# stm32-d40plus.net
KiCad netlist of a schematic drawn in EAGLE
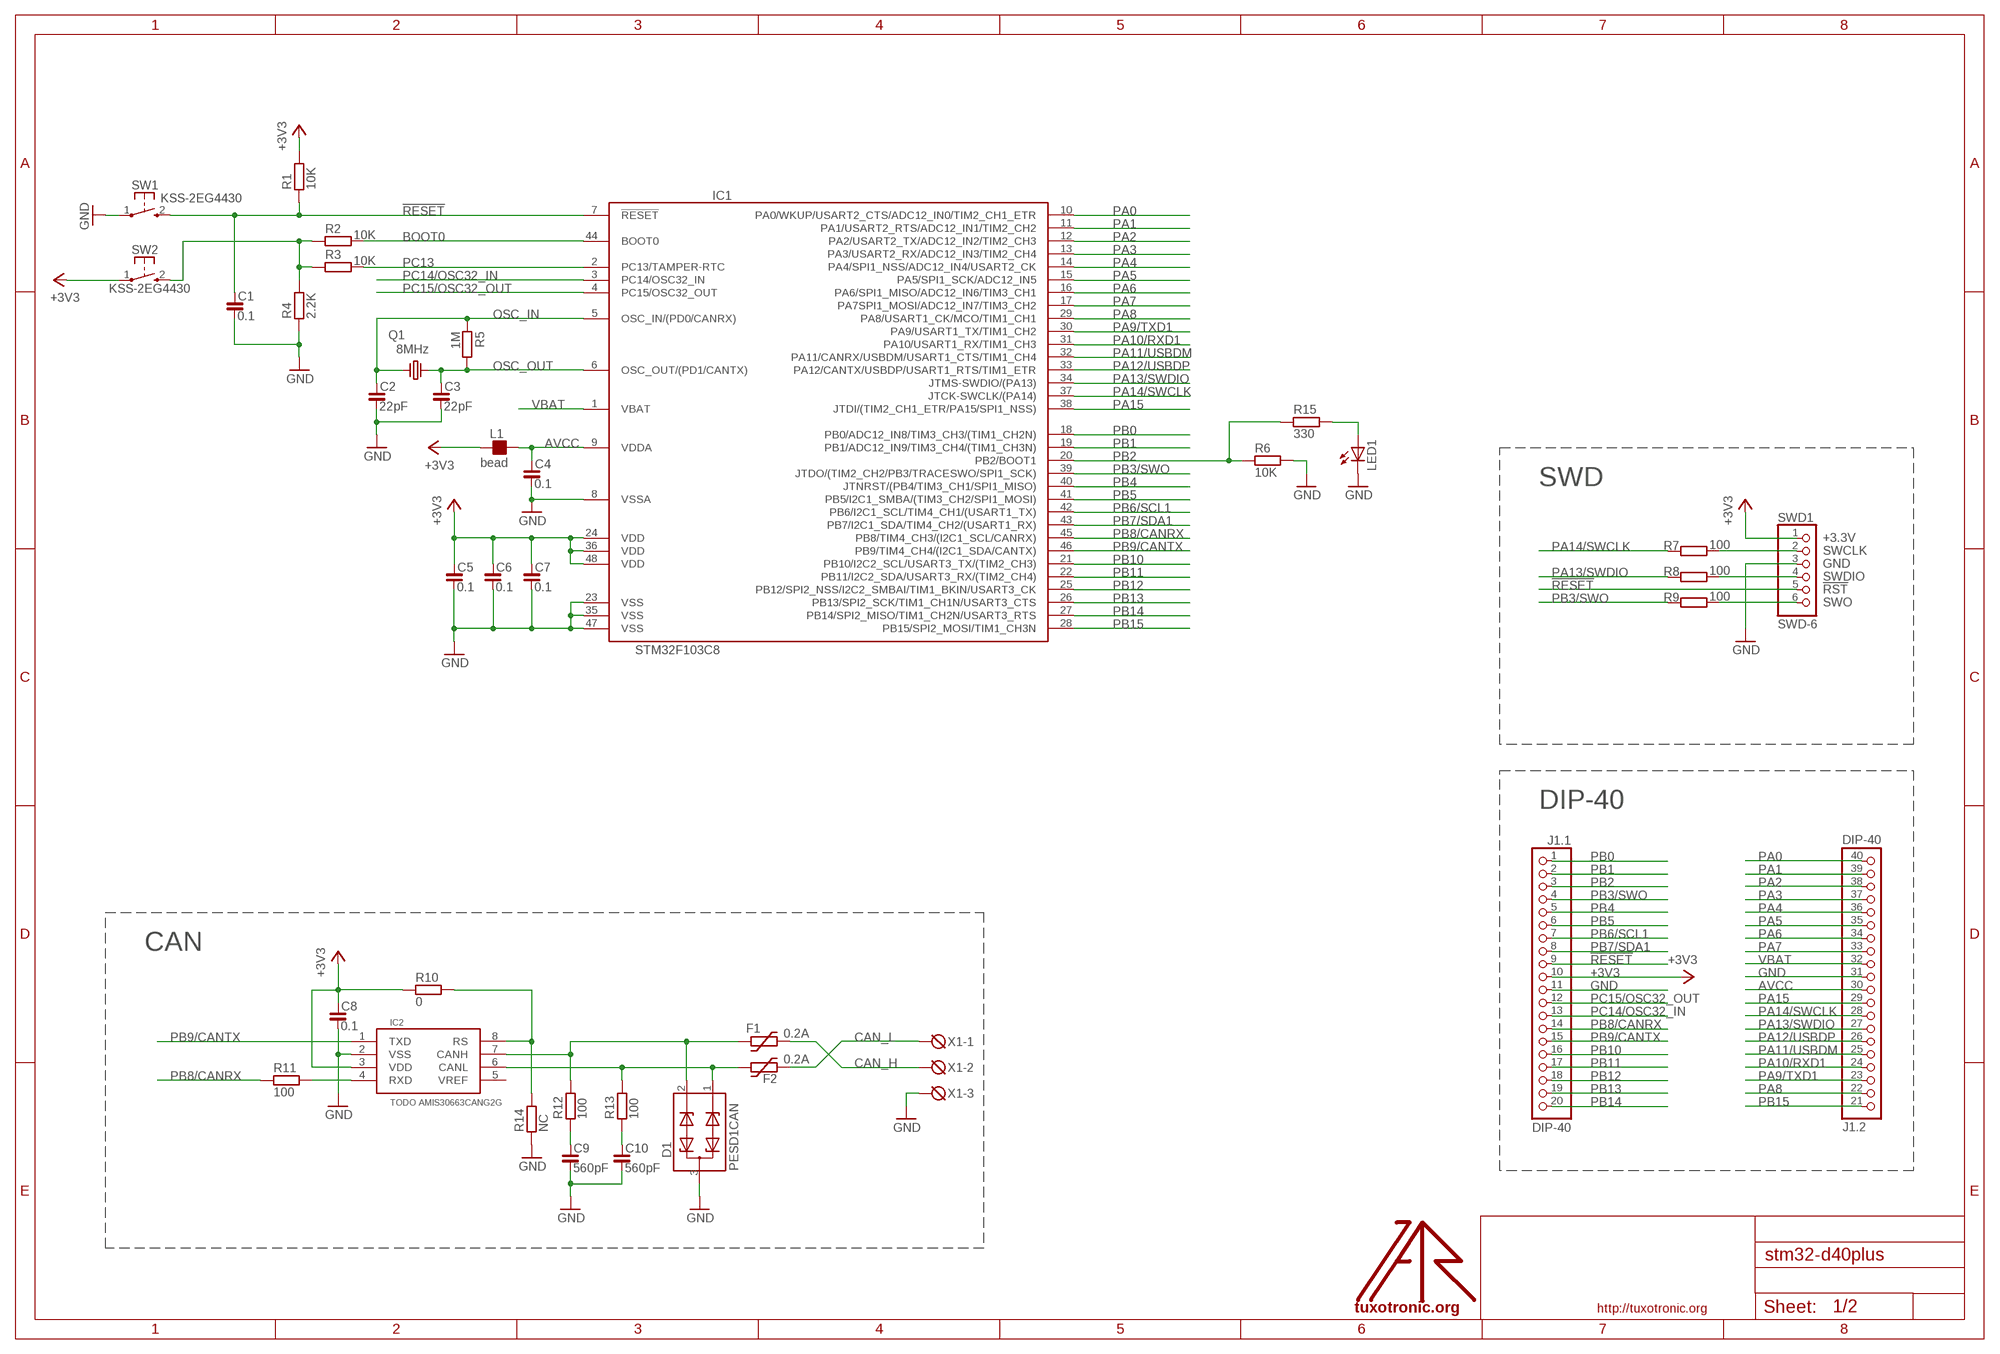
[diagram p0: schematic, sheet 1]
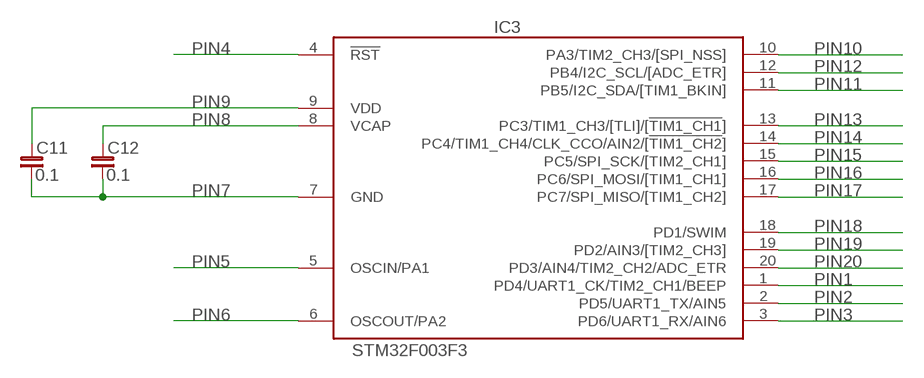
[diagram p1: schematic, sheet 2]

(export (version "E")
  (design (tool "Eeschema 10.0.6"))
  (components
    (comp (ref "C1")
      (value "0.1")
      (footprint "eagle-import:C0603")
      (libsource (lib "eagle-import") (part "C_0603"))
    )
    (comp (ref "C2")
      (value "22pF")
      (footprint "eagle-import:C0603")
      (libsource (lib "eagle-import") (part "C_0603"))
    )
    (comp (ref "C3")
      (value "22pF")
      (footprint "eagle-import:C0603")
      (libsource (lib "eagle-import") (part "C_0603"))
    )
    (comp (ref "C4")
      (value "0.1")
      (footprint "eagle-import:C0603")
      (libsource (lib "eagle-import") (part "C_0603"))
    )
    (comp (ref "C5")
      (value "0.1")
      (footprint "eagle-import:C0603")
      (libsource (lib "eagle-import") (part "C_0603"))
    )
    (comp (ref "C6")
      (value "0.1")
      (footprint "eagle-import:C0603")
      (libsource (lib "eagle-import") (part "C_0603"))
    )
    (comp (ref "C7")
      (value "0.1")
      (footprint "eagle-import:C0603")
      (libsource (lib "eagle-import") (part "C_0603"))
    )
    (comp (ref "C8")
      (value "0.1")
      (footprint "eagle-import:C0603")
      (libsource (lib "eagle-import") (part "C_0603"))
    )
    (comp (ref "C9")
      (value "560pF")
      (footprint "eagle-import:C0603")
      (libsource (lib "eagle-import") (part "C_0603"))
    )
    (comp (ref "C10")
      (value "560pF")
      (footprint "eagle-import:C0603")
      (libsource (lib "eagle-import") (part "C_0603"))
    )
    (comp (ref "D1")
      (value "PESD1CAN")
      (footprint "eagle-import:SOT23")
      (libsource (lib "eagle-import") (part "PESD1CAN"))
    )
    (comp (ref "F1")
      (value "0.2A")
      (footprint "eagle-import:1206L")
      (libsource (lib "eagle-import") (part "1206L"))
    )
    (comp (ref "F2")
      (value "0.2A")
      (footprint "eagle-import:1206L")
      (libsource (lib "eagle-import") (part "1206L"))
    )
    (comp (ref "IC1")
      (value "STM32F103C8")
      (footprint "eagle-import:LQFP48")
      (libsource (lib "eagle-import") (part "STM32F103C8"))
    )
    (comp (ref "IC2")
      (value "TODO AMIS30663CANG2G")
      (footprint "eagle-import:SO08")
      (libsource (lib "eagle-import") (part "SN65HVD230"))
    )
    (comp (ref "J1")
      (value "DIP-40")
      (footprint "eagle-import:DIP-40")
      (libsource (lib "eagle-import") (part "DIP-40"))
    )
    (comp (ref "L1")
      (value "bead")
      (footprint "eagle-import:L0603")
      (libsource (lib "eagle-import") (part "FB_0603"))
    )
    (comp (ref "LED1")
      (value "LEDCHIPLED_0603")
      (footprint "eagle-import:CHIPLED_0603")
      (libsource (lib "eagle-import") (part "LEDCHIPLED_0603"))
    )
    (comp (ref "Q1")
      (value "8MHz")
      (footprint "eagle-import:HC49_S")
      (libsource (lib "eagle-import") (part "CRYSTAL-HC49S"))
    )
    (comp (ref "R1")
      (value "10K")
      (footprint "eagle-import:R0603")
      (libsource (lib "eagle-import") (part "R_0603"))
    )
    (comp (ref "R2")
      (value "10K")
      (footprint "eagle-import:R0603")
      (libsource (lib "eagle-import") (part "R_0603"))
    )
    (comp (ref "R3")
      (value "10K")
      (footprint "eagle-import:R0603")
      (libsource (lib "eagle-import") (part "R_0603"))
    )
    (comp (ref "R4")
      (value "2.2K")
      (footprint "eagle-import:R0603")
      (libsource (lib "eagle-import") (part "R_0603"))
    )
    (comp (ref "R5")
      (value "1M")
      (footprint "eagle-import:R0603")
      (libsource (lib "eagle-import") (part "R_0603"))
    )
    (comp (ref "R6")
      (value "10K")
      (footprint "eagle-import:R0603")
      (libsource (lib "eagle-import") (part "R_0603"))
    )
    (comp (ref "R7")
      (value "100")
      (footprint "eagle-import:R0603")
      (libsource (lib "eagle-import") (part "R_0603"))
    )
    (comp (ref "R8")
      (value "100")
      (footprint "eagle-import:R0603")
      (libsource (lib "eagle-import") (part "R_0603"))
    )
    (comp (ref "R9")
      (value "100")
      (footprint "eagle-import:R0603")
      (libsource (lib "eagle-import") (part "R_0603"))
    )
    (comp (ref "R10")
      (value "0")
      (footprint "eagle-import:R0603")
      (libsource (lib "eagle-import") (part "R_0603"))
    )
    (comp (ref "R11")
      (value "100")
      (footprint "eagle-import:R0603")
      (libsource (lib "eagle-import") (part "R_0603"))
    )
    (comp (ref "R12")
      (value "100")
      (footprint "eagle-import:R0603")
      (libsource (lib "eagle-import") (part "R_0603"))
    )
    (comp (ref "R13")
      (value "100")
      (footprint "eagle-import:R0603")
      (libsource (lib "eagle-import") (part "R_0603"))
    )
    (comp (ref "R14")
      (value "NC")
      (footprint "eagle-import:R0603")
      (libsource (lib "eagle-import") (part "R_0603"))
    )
    (comp (ref "R15")
      (value "330")
      (footprint "eagle-import:R0603")
      (libsource (lib "eagle-import") (part "R_0603"))
    )
    (comp (ref "SW1")
      (value "KSS-2EG4430")
      (footprint "eagle-import:KSS-2EG4430")
      (libsource (lib "eagle-import") (part "KSS-2EG4430"))
    )
    (comp (ref "SW2")
      (value "KSS-2EG4430")
      (footprint "eagle-import:KSS-2EG4430")
      (libsource (lib "eagle-import") (part "KSS-2EG4430"))
    )
    (comp (ref "SWD1")
      (value "SWD-6")
      (footprint "eagle-import:JTAG6PIN")
      (libsource (lib "eagle-import") (part "SWD-6"))
    )
    (comp (ref "U$")
      (value "LOGO")
      (footprint "eagle-import:TT_LOGO")
      (libsource (lib "eagle-import") (part "LOGO"))
    )
    (comp (ref "X1")
      (value "DG3XX-03-3.5")
      (footprint "eagle-import:DG350-3.5-03P")
      (libsource (lib "eagle-import") (part "DG3XX-03-3.5"))
    )
    (comp (ref "C11")
      (value "0.1")
      (footprint "eagle-import:C0805")
      (libsource (lib "eagle-import") (part "C_0805"))
    )
    (comp (ref "C12")
      (value "0.1")
      (footprint "eagle-import:C0805")
      (libsource (lib "eagle-import") (part "C_0805"))
    )
    (comp (ref "IC3")
      (value "STM32F003F3")
      (footprint "eagle-import:TSSOP20")
      (libsource (lib "eagle-import") (part "STM32F003F3"))
    )
  )
  (nets
    (net (code "1") (name "+3V3") (class "Default")
      (node (ref "C5") (pin "1") (pinfunction "1_1") (pintype "passive"))
      (node (ref "C6") (pin "1") (pinfunction "1_1") (pintype "passive"))
      (node (ref "C7") (pin "1") (pinfunction "1_1") (pintype "passive"))
      (node (ref "C8") (pin "1") (pinfunction "1_1") (pintype "passive"))
      (node (ref "IC1") (pin "24") (pinfunction "VDD_24") (pintype "power_in"))
      (node (ref "IC1") (pin "36") (pinfunction "VDD_36") (pintype "power_in"))
      (node (ref "IC1") (pin "48") (pinfunction "VDD_48") (pintype "power_in"))
      (node (ref "IC2") (pin "3") (pinfunction "VDD_3") (pintype "power_in"))
      (node (ref "J1") (pin "10") (pinfunction "10_10") (pintype "passive"))
      (node (ref "L1") (pin "1") (pinfunction "1_1") (pintype "passive"))
      (node (ref "R1") (pin "2") (pinfunction "2_2") (pintype "passive"))
      (node (ref "R10") (pin "1") (pinfunction "1_1") (pintype "passive"))
      (node (ref "SW2") (pin "1") (pinfunction "P_1") (pintype "passive"))
      (node (ref "SWD1") (pin "1") (pinfunction "1_1") (pintype "passive"))
    )
    (net (code "2") (name "AVCC") (class "Default")
      (node (ref "C4") (pin "1") (pinfunction "1_1") (pintype "passive"))
      (node (ref "IC1") (pin "9") (pinfunction "VDDA_9") (pintype "power_in"))
      (node (ref "J1") (pin "30") (pinfunction "10_30") (pintype "passive"))
      (node (ref "L1") (pin "2") (pinfunction "2_2") (pintype "passive"))
    )
    (net (code "3") (name "BOOT0") (class "Default")
      (node (ref "IC1") (pin "44") (pinfunction "BOOT0_44") (pintype "input"))
      (node (ref "R2") (pin "2") (pinfunction "2_2") (pintype "passive"))
    )
    (net (code "4") (name "CAN_H") (class "Default")
      (node (ref "F1") (pin "P$2") (pinfunction "2_P$2") (pintype "passive"))
      (node (ref "X1") (pin "2") (pinfunction "KL_2") (pintype "passive"))
    )
    (net (code "5") (name "CAN_L") (class "Default")
      (node (ref "F2") (pin "P$2") (pinfunction "2_P$2") (pintype "passive"))
      (node (ref "X1") (pin "1") (pinfunction "KL_1") (pintype "passive"))
    )
    (net (code "6") (name "GND") (class "Default")
      (node (ref "C1") (pin "2") (pinfunction "2_2") (pintype "passive"))
      (node (ref "C10") (pin "2") (pinfunction "2_2") (pintype "passive"))
      (node (ref "C2") (pin "2") (pinfunction "2_2") (pintype "passive"))
      (node (ref "C3") (pin "2") (pinfunction "2_2") (pintype "passive"))
      (node (ref "C4") (pin "2") (pinfunction "2_2") (pintype "passive"))
      (node (ref "C5") (pin "2") (pinfunction "2_2") (pintype "passive"))
      (node (ref "C6") (pin "2") (pinfunction "2_2") (pintype "passive"))
      (node (ref "C7") (pin "2") (pinfunction "2_2") (pintype "passive"))
      (node (ref "C8") (pin "2") (pinfunction "2_2") (pintype "passive"))
      (node (ref "C9") (pin "2") (pinfunction "2_2") (pintype "passive"))
      (node (ref "D1") (pin "3") (pinfunction "3_3") (pintype "passive"))
      (node (ref "IC1") (pin "23") (pinfunction "VSS_23") (pintype "power_in"))
      (node (ref "IC1") (pin "35") (pinfunction "VSS_35") (pintype "power_in"))
      (node (ref "IC1") (pin "47") (pinfunction "VSS_47") (pintype "power_in"))
      (node (ref "IC1") (pin "8") (pinfunction "VSSA_8") (pintype "power_in"))
      (node (ref "IC2") (pin "2") (pinfunction "VSS_2") (pintype "power_in"))
      (node (ref "J1") (pin "11") (pinfunction "11_11") (pintype "passive"))
      (node (ref "J1") (pin "31") (pinfunction "11_31") (pintype "passive"))
      (node (ref "LED1") (pin "C") (pinfunction "C_C") (pintype "passive"))
      (node (ref "R14") (pin "1") (pinfunction "1_1") (pintype "passive"))
      (node (ref "R4") (pin "1") (pinfunction "1_1") (pintype "passive"))
      (node (ref "R6") (pin "2") (pinfunction "2_2") (pintype "passive"))
      (node (ref "SW1") (pin "1") (pinfunction "P_1") (pintype "passive"))
      (node (ref "SWD1") (pin "3") (pinfunction "3_3") (pintype "passive"))
      (node (ref "X1") (pin "3") (pinfunction "KL_3") (pintype "passive"))
    )
    (net (code "7") (name "Net-(C9-Pad1)") (class "Default")
      (node (ref "C9") (pin "1") (pinfunction "1_1") (pintype "passive"))
      (node (ref "R12") (pin "1") (pinfunction "1_1") (pintype "passive"))
    )
    (net (code "8") (name "Net-(C10-Pad1)") (class "Default")
      (node (ref "C10") (pin "1") (pinfunction "1_1") (pintype "passive"))
      (node (ref "R13") (pin "1") (pinfunction "1_1") (pintype "passive"))
    )
    (net (code "9") (name "Net-(F1-1)") (class "Default")
      (node (ref "D1") (pin "2") (pinfunction "2_2") (pintype "passive"))
      (node (ref "F1") (pin "P$1") (pinfunction "1_P$1") (pintype "passive"))
      (node (ref "IC2") (pin "7") (pinfunction "CANH_7") (pintype "bidirectional"))
      (node (ref "R12") (pin "2") (pinfunction "2_2") (pintype "passive"))
    )
    (net (code "10") (name "Net-(F2-1)") (class "Default")
      (node (ref "D1") (pin "1") (pinfunction "1_1") (pintype "passive"))
      (node (ref "F2") (pin "P$1") (pinfunction "1_P$1") (pintype "passive"))
      (node (ref "IC2") (pin "6") (pinfunction "CANL_6") (pintype "bidirectional"))
      (node (ref "R13") (pin "2") (pinfunction "2_2") (pintype "passive"))
    )
    (net (code "11") (name "Net-(IC2-RS)") (class "Default")
      (node (ref "IC2") (pin "8") (pinfunction "RS_8") (pintype "input"))
      (node (ref "R10") (pin "2") (pinfunction "2_2") (pintype "passive"))
      (node (ref "R14") (pin "2") (pinfunction "2_2") (pintype "passive"))
    )
    (net (code "12") (name "Net-(IC2-RXD)") (class "Default")
      (node (ref "IC2") (pin "4") (pinfunction "RXD_4") (pintype "output"))
      (node (ref "R11") (pin "2") (pinfunction "2_2") (pintype "passive"))
    )
    (net (code "13") (name "Net-(LED1-PadA)") (class "Default")
      (node (ref "LED1") (pin "A") (pinfunction "A_A") (pintype "passive"))
      (node (ref "R15") (pin "2") (pinfunction "2_2") (pintype "passive"))
    )
    (net (code "14") (name "Net-(R7-Pad2)") (class "Default")
      (node (ref "R7") (pin "2") (pinfunction "2_2") (pintype "passive"))
      (node (ref "SWD1") (pin "2") (pinfunction "2_2") (pintype "passive"))
    )
    (net (code "15") (name "Net-(R8-Pad2)") (class "Default")
      (node (ref "R8") (pin "2") (pinfunction "2_2") (pintype "passive"))
      (node (ref "SWD1") (pin "4") (pinfunction "4_4") (pintype "passive"))
    )
    (net (code "16") (name "Net-(R9-Pad2)") (class "Default")
      (node (ref "R9") (pin "2") (pinfunction "2_2") (pintype "passive"))
      (node (ref "SWD1") (pin "6") (pinfunction "6_6") (pintype "passive"))
    )
    (net (code "17") (name "Net-(SW2-S)") (class "Default")
      (node (ref "R2") (pin "1") (pinfunction "1_1") (pintype "passive"))
      (node (ref "R3") (pin "1") (pinfunction "1_1") (pintype "passive"))
      (node (ref "R4") (pin "2") (pinfunction "2_2") (pintype "passive"))
      (node (ref "SW2") (pin "2") (pinfunction "S_2") (pintype "passive"))
    )
    (net (code "18") (name "OSC_IN") (class "Default")
      (node (ref "C2") (pin "1") (pinfunction "1_1") (pintype "passive"))
      (node (ref "IC1") (pin "5") (pinfunction "OSC_IN/(PD0/CANRX)_5") (pintype "input"))
      (node (ref "Q1") (pin "1") (pinfunction "1_1") (pintype "passive"))
      (node (ref "R5") (pin "1") (pinfunction "1_1") (pintype "passive"))
    )
    (net (code "19") (name "OSC_OUT") (class "Default")
      (node (ref "C3") (pin "1") (pinfunction "1_1") (pintype "passive"))
      (node (ref "IC1") (pin "6") (pinfunction "OSC_OUT/(PD1/CANTX)_6") (pintype "output"))
      (node (ref "Q1") (pin "2") (pinfunction "2_2") (pintype "passive"))
      (node (ref "R5") (pin "2") (pinfunction "2_2") (pintype "passive"))
    )
    (net (code "20") (name "PA0") (class "Default")
      (node (ref "IC1") (pin "10") (pinfunction "PA0/WKUP/USART2_CTS/ADC12_IN0/TIM2_CH1_ETR_10") (pintype "bidirectional"))
      (node (ref "J1") (pin "40") (pinfunction "20_40") (pintype "passive"))
    )
    (net (code "21") (name "PA1") (class "Default")
      (node (ref "IC1") (pin "11") (pinfunction "PA1/USART2_RTS/ADC12_IN1/TIM2_CH2_11") (pintype "bidirectional"))
      (node (ref "J1") (pin "39") (pinfunction "19_39") (pintype "passive"))
    )
    (net (code "22") (name "PA2") (class "Default")
      (node (ref "IC1") (pin "12") (pinfunction "PA2/USART2_TX/ADC12_IN2/TIM2_CH3_12") (pintype "bidirectional"))
      (node (ref "J1") (pin "38") (pinfunction "18_38") (pintype "passive"))
    )
    (net (code "23") (name "PA3") (class "Default")
      (node (ref "IC1") (pin "13") (pinfunction "PA3/USART2_RX/ADC12_IN3/TIM2_CH4_13") (pintype "bidirectional"))
      (node (ref "J1") (pin "37") (pinfunction "17_37") (pintype "passive"))
    )
    (net (code "24") (name "PA4") (class "Default")
      (node (ref "IC1") (pin "14") (pinfunction "PA4/SPI1_NSS/ADC12_IN4/USART2_CK_14") (pintype "bidirectional"))
      (node (ref "J1") (pin "36") (pinfunction "16_36") (pintype "passive"))
    )
    (net (code "25") (name "PA5") (class "Default")
      (node (ref "IC1") (pin "15") (pinfunction "PA5/SPI1_SCK/ADC12_IN5_15") (pintype "bidirectional"))
      (node (ref "J1") (pin "35") (pinfunction "15_35") (pintype "passive"))
    )
    (net (code "26") (name "PA6") (class "Default")
      (node (ref "IC1") (pin "16") (pinfunction "PA6/SPI1_MISO/ADC12_IN6/TIM3_CH1_16") (pintype "bidirectional"))
      (node (ref "J1") (pin "34") (pinfunction "14_34") (pintype "passive"))
    )
    (net (code "27") (name "PA7") (class "Default")
      (node (ref "IC1") (pin "17") (pinfunction "PA7SPI1_MOSI/ADC12_IN7/TIM3_CH2_17") (pintype "bidirectional"))
      (node (ref "J1") (pin "33") (pinfunction "13_33") (pintype "passive"))
    )
    (net (code "28") (name "PA8") (class "Default")
      (node (ref "IC1") (pin "29") (pinfunction "PA8/USART1_CK/MCO/TIM1_CH1_29") (pintype "bidirectional"))
      (node (ref "J1") (pin "22") (pinfunction "2_22") (pintype "passive"))
    )
    (net (code "29") (name "PA9{slash}TXD1") (class "Default")
      (node (ref "IC1") (pin "30") (pinfunction "PA9/USART1_TX/TIM1_CH2_30") (pintype "bidirectional"))
      (node (ref "J1") (pin "23") (pinfunction "3_23") (pintype "passive"))
    )
    (net (code "30") (name "PA10{slash}RXD1") (class "Default")
      (node (ref "IC1") (pin "31") (pinfunction "PA10/USART1_RX/TIM1_CH3_31") (pintype "bidirectional"))
      (node (ref "J1") (pin "24") (pinfunction "4_24") (pintype "passive"))
    )
    (net (code "31") (name "PA11{slash}USBDM") (class "Default")
      (node (ref "IC1") (pin "32") (pinfunction "PA11/CANRX/USBDM/USART1_CTS/TIM1_CH4_32") (pintype "bidirectional"))
      (node (ref "J1") (pin "25") (pinfunction "5_25") (pintype "passive"))
    )
    (net (code "32") (name "PA12{slash}USBDP") (class "Default")
      (node (ref "IC1") (pin "33") (pinfunction "PA12/CANTX/USBDP/USART1_RTS/TIM1_ETR_33") (pintype "bidirectional"))
      (node (ref "J1") (pin "26") (pinfunction "6_26") (pintype "passive"))
    )
    (net (code "33") (name "PA13{slash}SWDIO") (class "Default")
      (node (ref "IC1") (pin "34") (pinfunction "JTMS-SWDIO/(PA13)_34") (pintype "bidirectional"))
      (node (ref "J1") (pin "27") (pinfunction "7_27") (pintype "passive"))
      (node (ref "R8") (pin "1") (pinfunction "1_1") (pintype "passive"))
    )
    (net (code "34") (name "PA14{slash}SWCLK") (class "Default")
      (node (ref "IC1") (pin "37") (pinfunction "JTCK-SWCLK/(PA14)_37") (pintype "bidirectional"))
      (node (ref "J1") (pin "28") (pinfunction "8_28") (pintype "passive"))
      (node (ref "R7") (pin "1") (pinfunction "1_1") (pintype "passive"))
    )
    (net (code "35") (name "PA15") (class "Default")
      (node (ref "IC1") (pin "38") (pinfunction "JTDI/(TIM2_CH1_ETR/PA15/SPI1_NSS)_38") (pintype "bidirectional"))
      (node (ref "J1") (pin "29") (pinfunction "9_29") (pintype "passive"))
    )
    (net (code "36") (name "PB0") (class "Default")
      (node (ref "IC1") (pin "18") (pinfunction "PB0/ADC12_IN8/TIM3_CH3/(TIM1_CH2N)_18") (pintype "bidirectional"))
      (node (ref "J1") (pin "1") (pinfunction "1_1") (pintype "passive"))
    )
    (net (code "37") (name "PB1") (class "Default")
      (node (ref "IC1") (pin "19") (pinfunction "PB1/ADC12_IN9/TIM3_CH4/(TIM1_CH3N)_19") (pintype "bidirectional"))
      (node (ref "J1") (pin "2") (pinfunction "2_2") (pintype "passive"))
    )
    (net (code "38") (name "PB2") (class "Default")
      (node (ref "IC1") (pin "20") (pinfunction "PB2/BOOT1_20") (pintype "bidirectional"))
      (node (ref "J1") (pin "3") (pinfunction "3_3") (pintype "passive"))
      (node (ref "R15") (pin "1") (pinfunction "1_1") (pintype "passive"))
      (node (ref "R6") (pin "1") (pinfunction "1_1") (pintype "passive"))
    )
    (net (code "39") (name "PB3{slash}SWO") (class "Default")
      (node (ref "IC1") (pin "39") (pinfunction "JTDO/(TIM2_CH2/PB3/TRACESWO/SPI1_SCK)_39") (pintype "bidirectional"))
      (node (ref "J1") (pin "4") (pinfunction "4_4") (pintype "passive"))
      (node (ref "R9") (pin "1") (pinfunction "1_1") (pintype "passive"))
    )
    (net (code "40") (name "PB4") (class "Default")
      (node (ref "IC1") (pin "40") (pinfunction "JTNRST/(PB4/TIM3_CH1/SPI1_MISO)_40") (pintype "bidirectional"))
      (node (ref "J1") (pin "5") (pinfunction "5_5") (pintype "passive"))
    )
    (net (code "41") (name "PB5") (class "Default")
      (node (ref "IC1") (pin "41") (pinfunction "PB5/I2C1_SMBA/(TIM3_CH2/SPI1_MOSI)_41") (pintype "bidirectional"))
      (node (ref "J1") (pin "6") (pinfunction "6_6") (pintype "passive"))
    )
    (net (code "42") (name "PB6{slash}SCL1") (class "Default")
      (node (ref "IC1") (pin "42") (pinfunction "PB6/I2C1_SCL/TIM4_CH1/(USART1_TX)_42") (pintype "bidirectional"))
      (node (ref "J1") (pin "7") (pinfunction "7_7") (pintype "passive"))
    )
    (net (code "43") (name "PB7{slash}SDA1") (class "Default")
      (node (ref "IC1") (pin "43") (pinfunction "PB7/I2C1_SDA/TIM4_CH2/(USART1_RX)_43") (pintype "bidirectional"))
      (node (ref "J1") (pin "8") (pinfunction "8_8") (pintype "passive"))
    )
    (net (code "44") (name "PB8{slash}CANRX") (class "Default")
      (node (ref "IC1") (pin "45") (pinfunction "PB8/TIM4_CH3/(I2C1_SCL/CANRX)_45") (pintype "bidirectional"))
      (node (ref "J1") (pin "14") (pinfunction "14_14") (pintype "passive"))
      (node (ref "R11") (pin "1") (pinfunction "1_1") (pintype "passive"))
    )
    (net (code "45") (name "PB9{slash}CANTX") (class "Default")
      (node (ref "IC1") (pin "46") (pinfunction "PB9/TIM4_CH4/(I2C1_SDA/CANTX)_46") (pintype "bidirectional"))
      (node (ref "IC2") (pin "1") (pinfunction "TXD_1") (pintype "input"))
      (node (ref "J1") (pin "15") (pinfunction "15_15") (pintype "passive"))
    )
    (net (code "46") (name "PB10") (class "Default")
      (node (ref "IC1") (pin "21") (pinfunction "PB10/I2C2_SCL/USART3_TX/(TIM2_CH3)_21") (pintype "bidirectional"))
      (node (ref "J1") (pin "16") (pinfunction "16_16") (pintype "passive"))
    )
    (net (code "47") (name "PB11") (class "Default")
      (node (ref "IC1") (pin "22") (pinfunction "PB11/I2C2_SDA/USART3_RX/(TIM2_CH4)_22") (pintype "bidirectional"))
      (node (ref "J1") (pin "17") (pinfunction "17_17") (pintype "passive"))
    )
    (net (code "48") (name "PB12") (class "Default")
      (node (ref "IC1") (pin "25") (pinfunction "PB12/SPI2_NSS/I2C2_SMBAI/TIM1_BKIN/USART3_CK_25") (pintype "bidirectional"))
      (node (ref "J1") (pin "18") (pinfunction "18_18") (pintype "passive"))
    )
    (net (code "49") (name "PB13") (class "Default")
      (node (ref "IC1") (pin "26") (pinfunction "PB13/SPI2_SCK/TIM1_CH1N/USART3_CTS_26") (pintype "bidirectional"))
      (node (ref "J1") (pin "19") (pinfunction "19_19") (pintype "passive"))
    )
    (net (code "50") (name "PB14") (class "Default")
      (node (ref "IC1") (pin "27") (pinfunction "PB14/SPI2_MISO/TIM1_CH2N/USART3_RTS_27") (pintype "bidirectional"))
      (node (ref "J1") (pin "20") (pinfunction "20_20") (pintype "passive"))
    )
    (net (code "51") (name "PB15") (class "Default")
      (node (ref "IC1") (pin "28") (pinfunction "PB15/SPI2_MOSI/TIM1_CH3N_28") (pintype "bidirectional"))
      (node (ref "J1") (pin "21") (pinfunction "1_21") (pintype "passive"))
    )
    (net (code "52") (name "PC13") (class "Default")
      (node (ref "IC1") (pin "2") (pinfunction "PC13/TAMPER-RTC_2") (pintype "bidirectional"))
      (node (ref "R3") (pin "2") (pinfunction "2_2") (pintype "passive"))
    )
    (net (code "53") (name "PC14{slash}OSC32_IN") (class "Default")
      (node (ref "IC1") (pin "3") (pinfunction "PC14/OSC32_IN_3") (pintype "bidirectional"))
      (node (ref "J1") (pin "13") (pinfunction "13_13") (pintype "passive"))
    )
    (net (code "54") (name "PC15{slash}OSC32_OUT") (class "Default")
      (node (ref "IC1") (pin "4") (pinfunction "PC15/OSC32_OUT_4") (pintype "bidirectional"))
      (node (ref "J1") (pin "12") (pinfunction "12_12") (pintype "passive"))
    )
    (net (code "55") (name "PIN1") (class "Default")
      (node (ref "IC3") (pin "1") (pinfunction "PD4/UART1_CK/TIM2_CH1/BEEP_1") (pintype "bidirectional"))
    )
    (net (code "56") (name "PIN2") (class "Default")
      (node (ref "IC3") (pin "2") (pinfunction "PD5/UART1_TX/AIN5_2") (pintype "bidirectional"))
    )
    (net (code "57") (name "PIN3") (class "Default")
      (node (ref "IC3") (pin "3") (pinfunction "PD6/UART1_RX/AIN6_3") (pintype "bidirectional"))
    )
    (net (code "58") (name "PIN4") (class "Default")
      (node (ref "IC3") (pin "4") (pinfunction "~{RST}_4") (pintype "input"))
    )
    (net (code "59") (name "PIN5") (class "Default")
      (node (ref "IC3") (pin "5") (pinfunction "OSCIN/PA1_5") (pintype "bidirectional"))
    )
    (net (code "60") (name "PIN6") (class "Default")
      (node (ref "IC3") (pin "6") (pinfunction "OSCOUT/PA2_6") (pintype "bidirectional"))
    )
    (net (code "61") (name "PIN7") (class "Default")
      (node (ref "C11") (pin "2") (pinfunction "2_2") (pintype "passive"))
      (node (ref "C12") (pin "2") (pinfunction "2_2") (pintype "passive"))
      (node (ref "IC3") (pin "7") (pinfunction "GND_7") (pintype "power_in"))
    )
    (net (code "62") (name "PIN8") (class "Default")
      (node (ref "C12") (pin "1") (pinfunction "1_1") (pintype "passive"))
      (node (ref "IC3") (pin "8") (pinfunction "VCAP_8") (pintype "power_in"))
    )
    (net (code "63") (name "PIN9") (class "Default")
      (node (ref "C11") (pin "1") (pinfunction "1_1") (pintype "passive"))
      (node (ref "IC3") (pin "9") (pinfunction "VDD_9") (pintype "power_in"))
    )
    (net (code "64") (name "PIN10") (class "Default")
      (node (ref "IC3") (pin "10") (pinfunction "PA3/TIM2_CH3/[SPI_NSS]_10") (pintype "bidirectional"))
    )
    (net (code "65") (name "PIN11") (class "Default")
      (node (ref "IC3") (pin "11") (pinfunction "PB5/I2C_SDA/[TIM1_BKIN]_11") (pintype "bidirectional"))
    )
    (net (code "66") (name "PIN12") (class "Default")
      (node (ref "IC3") (pin "12") (pinfunction "PB4/I2C_SCL/[ADC_ETR]_12") (pintype "bidirectional"))
    )
    (net (code "67") (name "PIN13") (class "Default")
      (node (ref "IC3") (pin "13") (pinfunction "PC3/TIM1_CH3/[TLI]/[~{TIM1_CH1}]_13") (pintype "bidirectional"))
    )
    (net (code "68") (name "PIN14") (class "Default")
      (node (ref "IC3") (pin "14") (pinfunction "PC4/TIM1_CH4/CLK_CCO/AIN2/[~{TIM1_CH2}]_14") (pintype "bidirectional"))
    )
    (net (code "69") (name "PIN15") (class "Default")
      (node (ref "IC3") (pin "15") (pinfunction "PC5/SPI_SCK/[TIM2_CH1]_15") (pintype "bidirectional"))
    )
    (net (code "70") (name "PIN16") (class "Default")
      (node (ref "IC3") (pin "16") (pinfunction "PC6/SPI_MOSI/[TIM1_CH1]_16") (pintype "bidirectional"))
    )
    (net (code "71") (name "PIN17") (class "Default")
      (node (ref "IC3") (pin "17") (pinfunction "PC7/SPI_MISO/[TIM1_CH2]_17") (pintype "bidirectional"))
    )
    (net (code "72") (name "PIN18") (class "Default")
      (node (ref "IC3") (pin "18") (pinfunction "PD1/SWIM_18") (pintype "bidirectional"))
    )
    (net (code "73") (name "PIN19") (class "Default")
      (node (ref "IC3") (pin "19") (pinfunction "PD2/AIN3/[TIM2_CH3]_19") (pintype "bidirectional"))
    )
    (net (code "74") (name "PIN20") (class "Default")
      (node (ref "IC3") (pin "20") (pinfunction "PD3/AIN4/TIM2_CH2/ADC_ETR_20") (pintype "bidirectional"))
    )
    (net (code "75") (name "VBAT") (class "Default")
      (node (ref "IC1") (pin "1") (pinfunction "VBAT_1") (pintype "power_in"))
      (node (ref "J1") (pin "32") (pinfunction "12_32") (pintype "passive"))
    )
    (net (code "76") (name "unconnected-(IC2-VREF-Pad5)") (class "Default")
      (node (ref "IC2") (pin "5") (pinfunction "VREF_5") (pintype "passive"))
    )
    (net (code "77") (name "~{RESET}") (class "Default")
      (node (ref "C1") (pin "1") (pinfunction "1_1") (pintype "passive"))
      (node (ref "IC1") (pin "7") (pinfunction "~{RESET}_7") (pintype "input"))
      (node (ref "J1") (pin "9") (pinfunction "9_9") (pintype "passive"))
      (node (ref "R1") (pin "1") (pinfunction "1_1") (pintype "passive"))
      (node (ref "SW1") (pin "2") (pinfunction "S_2") (pintype "passive"))
      (node (ref "SWD1") (pin "5") (pinfunction "5_5") (pintype "passive"))
    )
  )
)
